# BMS_Adapter_Segment.net
KiCad netlist of a schematic drawn in EAGLE
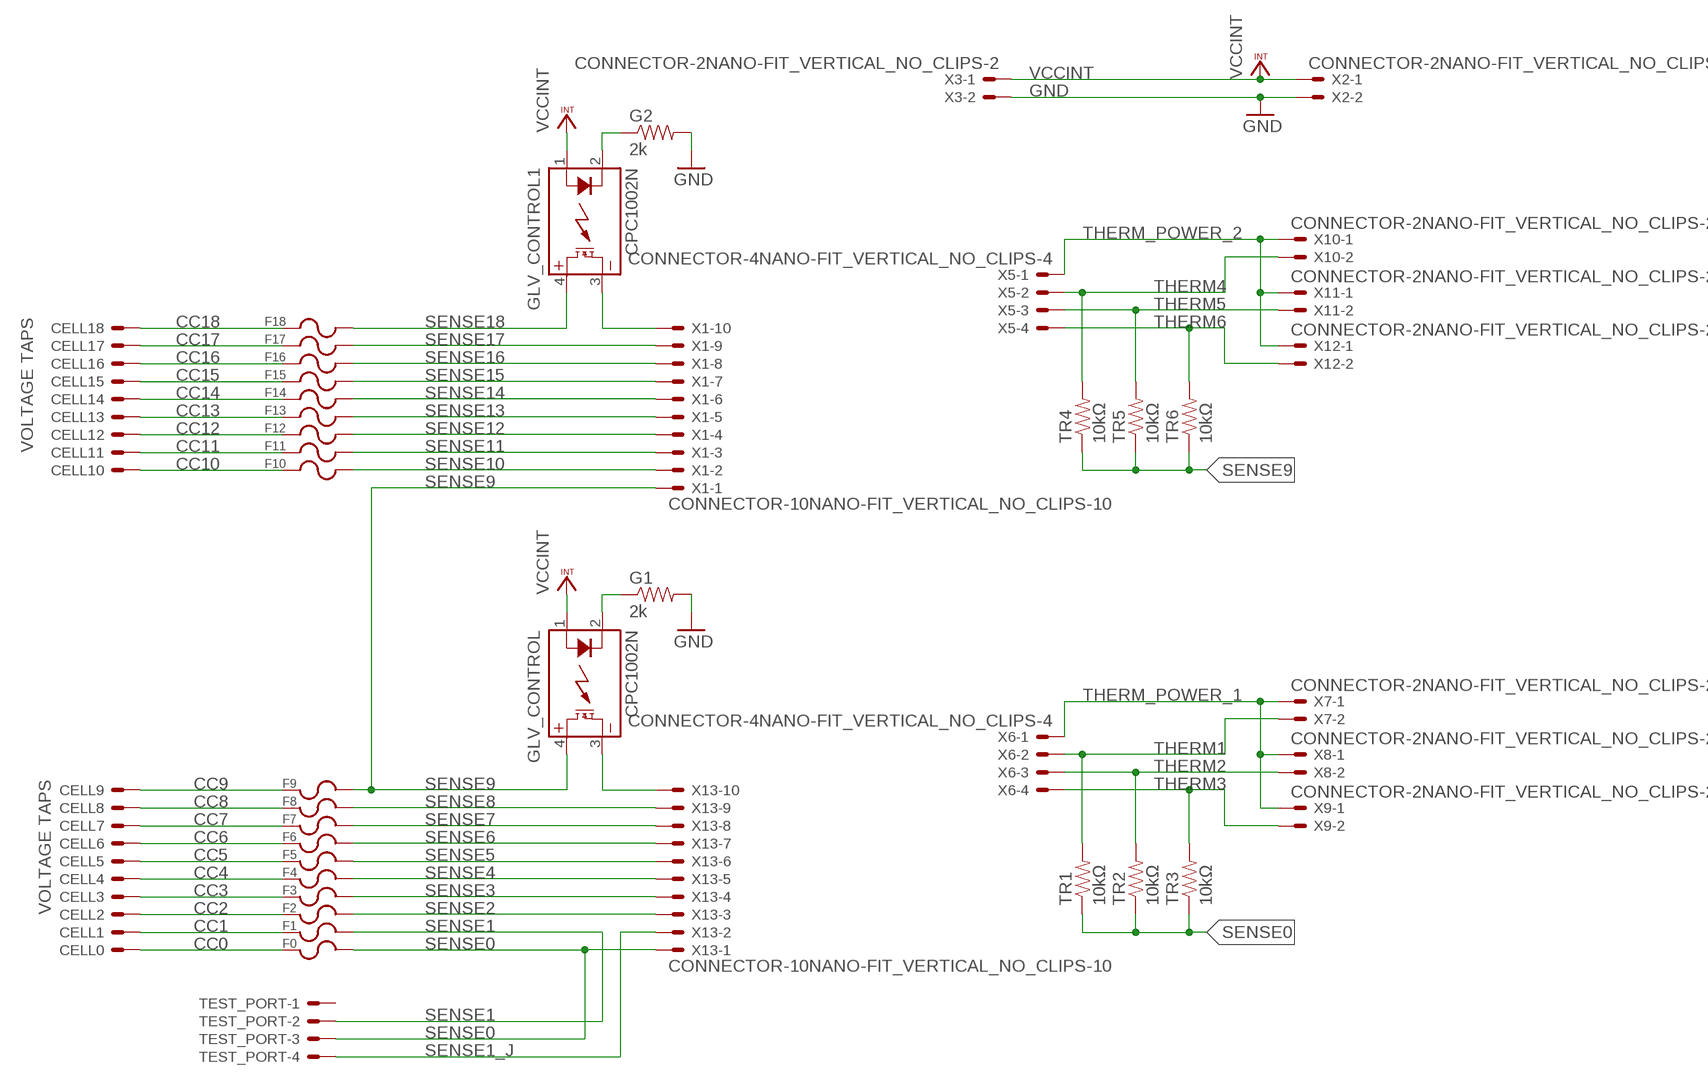
[diagram p0: schematic, sheet 1]

(export (version "E")
  (design (tool "Eeschema 10.0.6"))
  (components
    (comp (ref "CELL0")
      (value "BATTERY_SPRING_KEYSTONE5222")
      (footprint "eagle-import:KEYSTONE5222")
      (libsource (lib "eagle-import") (part "BATTERY_SPRING_KEYSTONE5222"))
    )
    (comp (ref "CELL1")
      (value "BATTERY_SPRING_KEYSTONE5222")
      (footprint "eagle-import:KEYSTONE5222")
      (libsource (lib "eagle-import") (part "BATTERY_SPRING_KEYSTONE5222"))
    )
    (comp (ref "CELL2")
      (value "BATTERY_SPRING_KEYSTONE5222")
      (footprint "eagle-import:KEYSTONE5222")
      (libsource (lib "eagle-import") (part "BATTERY_SPRING_KEYSTONE5222"))
    )
    (comp (ref "CELL3")
      (value "BATTERY_SPRING_KEYSTONE5222")
      (footprint "eagle-import:KEYSTONE5222")
      (libsource (lib "eagle-import") (part "BATTERY_SPRING_KEYSTONE5222"))
    )
    (comp (ref "CELL4")
      (value "BATTERY_SPRING_KEYSTONE5222")
      (footprint "eagle-import:KEYSTONE5222")
      (libsource (lib "eagle-import") (part "BATTERY_SPRING_KEYSTONE5222"))
    )
    (comp (ref "CELL5")
      (value "BATTERY_SPRING_KEYSTONE5222")
      (footprint "eagle-import:KEYSTONE5222")
      (libsource (lib "eagle-import") (part "BATTERY_SPRING_KEYSTONE5222"))
    )
    (comp (ref "CELL6")
      (value "BATTERY_SPRING_KEYSTONE5222")
      (footprint "eagle-import:KEYSTONE5222")
      (libsource (lib "eagle-import") (part "BATTERY_SPRING_KEYSTONE5222"))
    )
    (comp (ref "CELL7")
      (value "BATTERY_SPRING_KEYSTONE5222")
      (footprint "eagle-import:KEYSTONE5222")
      (libsource (lib "eagle-import") (part "BATTERY_SPRING_KEYSTONE5222"))
    )
    (comp (ref "CELL8")
      (value "BATTERY_SPRING_KEYSTONE5222")
      (footprint "eagle-import:KEYSTONE5222")
      (libsource (lib "eagle-import") (part "BATTERY_SPRING_KEYSTONE5222"))
    )
    (comp (ref "CELL9")
      (value "BATTERY_SPRING_KEYSTONE5222")
      (footprint "eagle-import:KEYSTONE5222")
      (libsource (lib "eagle-import") (part "BATTERY_SPRING_KEYSTONE5222"))
    )
    (comp (ref "CELL10")
      (value "BATTERY_SPRING_KEYSTONE5222")
      (footprint "eagle-import:KEYSTONE5222")
      (libsource (lib "eagle-import") (part "BATTERY_SPRING_KEYSTONE5222"))
    )
    (comp (ref "CELL11")
      (value "BATTERY_SPRING_KEYSTONE5222")
      (footprint "eagle-import:KEYSTONE5222")
      (libsource (lib "eagle-import") (part "BATTERY_SPRING_KEYSTONE5222"))
    )
    (comp (ref "CELL12")
      (value "BATTERY_SPRING_KEYSTONE5222")
      (footprint "eagle-import:KEYSTONE5222")
      (libsource (lib "eagle-import") (part "BATTERY_SPRING_KEYSTONE5222"))
    )
    (comp (ref "CELL13")
      (value "BATTERY_SPRING_KEYSTONE5222")
      (footprint "eagle-import:KEYSTONE5222")
      (libsource (lib "eagle-import") (part "BATTERY_SPRING_KEYSTONE5222"))
    )
    (comp (ref "CELL14")
      (value "BATTERY_SPRING_KEYSTONE5222")
      (footprint "eagle-import:KEYSTONE5222")
      (libsource (lib "eagle-import") (part "BATTERY_SPRING_KEYSTONE5222"))
    )
    (comp (ref "CELL15")
      (value "BATTERY_SPRING_KEYSTONE5222")
      (footprint "eagle-import:KEYSTONE5222")
      (libsource (lib "eagle-import") (part "BATTERY_SPRING_KEYSTONE5222"))
    )
    (comp (ref "CELL16")
      (value "BATTERY_SPRING_KEYSTONE5222")
      (footprint "eagle-import:KEYSTONE5222")
      (libsource (lib "eagle-import") (part "BATTERY_SPRING_KEYSTONE5222"))
    )
    (comp (ref "CELL17")
      (value "BATTERY_SPRING_KEYSTONE5222")
      (footprint "eagle-import:KEYSTONE5222")
      (libsource (lib "eagle-import") (part "BATTERY_SPRING_KEYSTONE5222"))
    )
    (comp (ref "CELL18")
      (value "BATTERY_SPRING_KEYSTONE5222")
      (footprint "eagle-import:KEYSTONE5222")
      (libsource (lib "eagle-import") (part "BATTERY_SPRING_KEYSTONE5222"))
    )
    (comp (ref "F0")
      (value "0751.0110_FUSE_CLIP")
      (footprint "eagle-import:0751.0110")
      (libsource (lib "eagle-import") (part "0751.0110_FUSE_CLIP"))
    )
    (comp (ref "F1")
      (value "0751.0110_FUSE_CLIP")
      (footprint "eagle-import:0751.0110")
      (libsource (lib "eagle-import") (part "0751.0110_FUSE_CLIP"))
    )
    (comp (ref "F2")
      (value "0751.0110_FUSE_CLIP")
      (footprint "eagle-import:0751.0110")
      (libsource (lib "eagle-import") (part "0751.0110_FUSE_CLIP"))
    )
    (comp (ref "F3")
      (value "0751.0110_FUSE_CLIP")
      (footprint "eagle-import:0751.0110")
      (libsource (lib "eagle-import") (part "0751.0110_FUSE_CLIP"))
    )
    (comp (ref "F4")
      (value "0751.0110_FUSE_CLIP")
      (footprint "eagle-import:0751.0110")
      (libsource (lib "eagle-import") (part "0751.0110_FUSE_CLIP"))
    )
    (comp (ref "F5")
      (value "0751.0110_FUSE_CLIP")
      (footprint "eagle-import:0751.0110")
      (libsource (lib "eagle-import") (part "0751.0110_FUSE_CLIP"))
    )
    (comp (ref "F6")
      (value "0751.0110_FUSE_CLIP")
      (footprint "eagle-import:0751.0110")
      (libsource (lib "eagle-import") (part "0751.0110_FUSE_CLIP"))
    )
    (comp (ref "F7")
      (value "0751.0110_FUSE_CLIP")
      (footprint "eagle-import:0751.0110")
      (libsource (lib "eagle-import") (part "0751.0110_FUSE_CLIP"))
    )
    (comp (ref "F8")
      (value "0751.0110_FUSE_CLIP")
      (footprint "eagle-import:0751.0110")
      (libsource (lib "eagle-import") (part "0751.0110_FUSE_CLIP"))
    )
    (comp (ref "F9")
      (value "0751.0110_FUSE_CLIP")
      (footprint "eagle-import:0751.0110")
      (libsource (lib "eagle-import") (part "0751.0110_FUSE_CLIP"))
    )
    (comp (ref "F10")
      (value "0751.0110_FUSE_CLIP")
      (footprint "eagle-import:0751.0110")
      (libsource (lib "eagle-import") (part "0751.0110_FUSE_CLIP"))
    )
    (comp (ref "F11")
      (value "0751.0110_FUSE_CLIP")
      (footprint "eagle-import:0751.0110")
      (libsource (lib "eagle-import") (part "0751.0110_FUSE_CLIP"))
    )
    (comp (ref "F12")
      (value "0751.0110_FUSE_CLIP")
      (footprint "eagle-import:0751.0110")
      (libsource (lib "eagle-import") (part "0751.0110_FUSE_CLIP"))
    )
    (comp (ref "F13")
      (value "0751.0110_FUSE_CLIP")
      (footprint "eagle-import:0751.0110")
      (libsource (lib "eagle-import") (part "0751.0110_FUSE_CLIP"))
    )
    (comp (ref "F14")
      (value "0751.0110_FUSE_CLIP")
      (footprint "eagle-import:0751.0110")
      (libsource (lib "eagle-import") (part "0751.0110_FUSE_CLIP"))
    )
    (comp (ref "F15")
      (value "0751.0110_FUSE_CLIP")
      (footprint "eagle-import:0751.0110")
      (libsource (lib "eagle-import") (part "0751.0110_FUSE_CLIP"))
    )
    (comp (ref "F16")
      (value "0751.0110_FUSE_CLIP")
      (footprint "eagle-import:0751.0110")
      (libsource (lib "eagle-import") (part "0751.0110_FUSE_CLIP"))
    )
    (comp (ref "F17")
      (value "0751.0110_FUSE_CLIP")
      (footprint "eagle-import:0751.0110")
      (libsource (lib "eagle-import") (part "0751.0110_FUSE_CLIP"))
    )
    (comp (ref "F18")
      (value "0751.0110_FUSE_CLIP")
      (footprint "eagle-import:0751.0110")
      (libsource (lib "eagle-import") (part "0751.0110_FUSE_CLIP"))
    )
    (comp (ref "G1")
      (value "2k")
      (footprint "eagle-import:0805")
      (libsource (lib "eagle-import") (part "RESISTOR0805-RES"))
    )
    (comp (ref "G2")
      (value "2k")
      (footprint "eagle-import:0805")
      (libsource (lib "eagle-import") (part "RESISTOR0805-RES"))
    )
    (comp (ref "GLV_CONTROL")
      (value "CPC1002N")
      (footprint "eagle-import:SOP04")
      (libsource (lib "eagle-import") (part "CPC1002N"))
    )
    (comp (ref "GLV_CONTROL1")
      (value "CPC1002N")
      (footprint "eagle-import:SOP04")
      (libsource (lib "eagle-import") (part "CPC1002N"))
    )
    (comp (ref "TEST_PORT")
      (value "MINIFIT_5566-4")
      (footprint "eagle-import:MINIFIT_5566-4")
      (libsource (lib "eagle-import") (part "MINIFIT_5566-4"))
    )
    (comp (ref "TR1")
      (value "10kΩ")
      (footprint "eagle-import:0805")
      (libsource (lib "eagle-import") (part "RESISTOR0805-RES"))
    )
    (comp (ref "TR2")
      (value "10kΩ")
      (footprint "eagle-import:0805")
      (libsource (lib "eagle-import") (part "RESISTOR0805-RES"))
    )
    (comp (ref "TR3")
      (value "10kΩ")
      (footprint "eagle-import:0805")
      (libsource (lib "eagle-import") (part "RESISTOR0805-RES"))
    )
    (comp (ref "TR4")
      (value "10kΩ")
      (footprint "eagle-import:0805")
      (libsource (lib "eagle-import") (part "RESISTOR0805-RES"))
    )
    (comp (ref "TR5")
      (value "10kΩ")
      (footprint "eagle-import:0805")
      (libsource (lib "eagle-import") (part "RESISTOR0805-RES"))
    )
    (comp (ref "TR6")
      (value "10kΩ")
      (footprint "eagle-import:0805")
      (libsource (lib "eagle-import") (part "RESISTOR0805-RES"))
    )
    (comp (ref "X1")
      (value "CONNECTOR-10NANO-FIT_VERTICAL_NO_CLIPS-10")
      (footprint "eagle-import:NANO-FIT_VERTICAL_NO_CLIPS-10")
      (libsource (lib "eagle-import") (part "CONNECTOR-10NANO-FIT_VERTICAL_NO_CLIPS-10"))
    )
    (comp (ref "X2")
      (value "CONNECTOR-2NANO-FIT_VERTICAL_NO_CLIPS-2")
      (footprint "eagle-import:NANO-FIT_VERTICAL_NO_CLIPS-2")
      (libsource (lib "eagle-import") (part "CONNECTOR-2NANO-FIT_VERTICAL_NO_CLIPS-2"))
    )
    (comp (ref "X3")
      (value "CONNECTOR-2NANO-FIT_VERTICAL_NO_CLIPS-2")
      (footprint "eagle-import:NANO-FIT_VERTICAL_NO_CLIPS-2")
      (libsource (lib "eagle-import") (part "CONNECTOR-2NANO-FIT_VERTICAL_NO_CLIPS-2"))
    )
    (comp (ref "X5")
      (value "CONNECTOR-4NANO-FIT_VERTICAL_NO_CLIPS-4")
      (footprint "eagle-import:NANO-FIT_VERTICAL_NO_CLIPS-4")
      (libsource (lib "eagle-import") (part "CONNECTOR-4NANO-FIT_VERTICAL_NO_CLIPS-4"))
    )
    (comp (ref "X6")
      (value "CONNECTOR-4NANO-FIT_VERTICAL_NO_CLIPS-4")
      (footprint "eagle-import:NANO-FIT_VERTICAL_NO_CLIPS-4")
      (libsource (lib "eagle-import") (part "CONNECTOR-4NANO-FIT_VERTICAL_NO_CLIPS-4"))
    )
    (comp (ref "X7")
      (value "CONNECTOR-2NANO-FIT_VERTICAL_NO_CLIPS-2")
      (footprint "eagle-import:NANO-FIT_VERTICAL_NO_CLIPS-2")
      (libsource (lib "eagle-import") (part "CONNECTOR-2NANO-FIT_VERTICAL_NO_CLIPS-2"))
    )
    (comp (ref "X8")
      (value "CONNECTOR-2NANO-FIT_VERTICAL_NO_CLIPS-2")
      (footprint "eagle-import:NANO-FIT_VERTICAL_NO_CLIPS-2")
      (libsource (lib "eagle-import") (part "CONNECTOR-2NANO-FIT_VERTICAL_NO_CLIPS-2"))
    )
    (comp (ref "X9")
      (value "CONNECTOR-2NANO-FIT_VERTICAL_NO_CLIPS-2")
      (footprint "eagle-import:NANO-FIT_VERTICAL_NO_CLIPS-2")
      (libsource (lib "eagle-import") (part "CONNECTOR-2NANO-FIT_VERTICAL_NO_CLIPS-2"))
    )
    (comp (ref "X10")
      (value "CONNECTOR-2NANO-FIT_VERTICAL_NO_CLIPS-2")
      (footprint "eagle-import:NANO-FIT_VERTICAL_NO_CLIPS-2")
      (libsource (lib "eagle-import") (part "CONNECTOR-2NANO-FIT_VERTICAL_NO_CLIPS-2"))
    )
    (comp (ref "X11")
      (value "CONNECTOR-2NANO-FIT_VERTICAL_NO_CLIPS-2")
      (footprint "eagle-import:NANO-FIT_VERTICAL_NO_CLIPS-2")
      (libsource (lib "eagle-import") (part "CONNECTOR-2NANO-FIT_VERTICAL_NO_CLIPS-2"))
    )
    (comp (ref "X12")
      (value "CONNECTOR-2NANO-FIT_VERTICAL_NO_CLIPS-2")
      (footprint "eagle-import:NANO-FIT_VERTICAL_NO_CLIPS-2")
      (libsource (lib "eagle-import") (part "CONNECTOR-2NANO-FIT_VERTICAL_NO_CLIPS-2"))
    )
    (comp (ref "X13")
      (value "CONNECTOR-10NANO-FIT_VERTICAL_NO_CLIPS-10")
      (footprint "eagle-import:NANO-FIT_VERTICAL_NO_CLIPS-10")
      (libsource (lib "eagle-import") (part "CONNECTOR-10NANO-FIT_VERTICAL_NO_CLIPS-10"))
    )
  )
  (nets
    (net (code "1") (name "/CC0") (class "Default")
      (node (ref "CELL0") (pin "P$1") (pinfunction "S_P$1") (pintype "passive"))
      (node (ref "F0") (pin "L1") (pinfunction "1_L1") (pintype "bidirectional"))
      (node (ref "F0") (pin "L2") (pinfunction "1_L2") (pintype "bidirectional"))
    )
    (net (code "2") (name "/CC1") (class "Default")
      (node (ref "CELL1") (pin "P$1") (pinfunction "S_P$1") (pintype "passive"))
      (node (ref "F1") (pin "L1") (pinfunction "1_L1") (pintype "bidirectional"))
      (node (ref "F1") (pin "L2") (pinfunction "1_L2") (pintype "bidirectional"))
    )
    (net (code "3") (name "/CC2") (class "Default")
      (node (ref "CELL2") (pin "P$1") (pinfunction "S_P$1") (pintype "passive"))
      (node (ref "F2") (pin "L1") (pinfunction "1_L1") (pintype "bidirectional"))
      (node (ref "F2") (pin "L2") (pinfunction "1_L2") (pintype "bidirectional"))
    )
    (net (code "4") (name "/CC3") (class "Default")
      (node (ref "CELL3") (pin "P$1") (pinfunction "S_P$1") (pintype "passive"))
      (node (ref "F3") (pin "L1") (pinfunction "1_L1") (pintype "bidirectional"))
      (node (ref "F3") (pin "L2") (pinfunction "1_L2") (pintype "bidirectional"))
    )
    (net (code "5") (name "/CC4") (class "Default")
      (node (ref "CELL4") (pin "P$1") (pinfunction "S_P$1") (pintype "passive"))
      (node (ref "F4") (pin "L1") (pinfunction "1_L1") (pintype "bidirectional"))
      (node (ref "F4") (pin "L2") (pinfunction "1_L2") (pintype "bidirectional"))
    )
    (net (code "6") (name "/CC5") (class "Default")
      (node (ref "CELL5") (pin "P$1") (pinfunction "S_P$1") (pintype "passive"))
      (node (ref "F5") (pin "L1") (pinfunction "1_L1") (pintype "bidirectional"))
      (node (ref "F5") (pin "L2") (pinfunction "1_L2") (pintype "bidirectional"))
    )
    (net (code "7") (name "/CC6") (class "Default")
      (node (ref "CELL6") (pin "P$1") (pinfunction "S_P$1") (pintype "passive"))
      (node (ref "F6") (pin "L1") (pinfunction "1_L1") (pintype "bidirectional"))
      (node (ref "F6") (pin "L2") (pinfunction "1_L2") (pintype "bidirectional"))
    )
    (net (code "8") (name "/CC7") (class "Default")
      (node (ref "CELL7") (pin "P$1") (pinfunction "S_P$1") (pintype "passive"))
      (node (ref "F7") (pin "L1") (pinfunction "1_L1") (pintype "bidirectional"))
      (node (ref "F7") (pin "L2") (pinfunction "1_L2") (pintype "bidirectional"))
    )
    (net (code "9") (name "/CC8") (class "Default")
      (node (ref "CELL8") (pin "P$1") (pinfunction "S_P$1") (pintype "passive"))
      (node (ref "F8") (pin "L1") (pinfunction "1_L1") (pintype "bidirectional"))
      (node (ref "F8") (pin "L2") (pinfunction "1_L2") (pintype "bidirectional"))
    )
    (net (code "10") (name "/CC9") (class "Default")
      (node (ref "CELL9") (pin "P$1") (pinfunction "S_P$1") (pintype "passive"))
      (node (ref "F9") (pin "L1") (pinfunction "1_L1") (pintype "bidirectional"))
      (node (ref "F9") (pin "L2") (pinfunction "1_L2") (pintype "bidirectional"))
    )
    (net (code "11") (name "/CC10") (class "Default")
      (node (ref "CELL10") (pin "P$1") (pinfunction "S_P$1") (pintype "passive"))
      (node (ref "F10") (pin "L1") (pinfunction "1_L1") (pintype "bidirectional"))
      (node (ref "F10") (pin "L2") (pinfunction "1_L2") (pintype "bidirectional"))
    )
    (net (code "12") (name "/CC11") (class "Default")
      (node (ref "CELL11") (pin "P$1") (pinfunction "S_P$1") (pintype "passive"))
      (node (ref "F11") (pin "L1") (pinfunction "1_L1") (pintype "bidirectional"))
      (node (ref "F11") (pin "L2") (pinfunction "1_L2") (pintype "bidirectional"))
    )
    (net (code "13") (name "/CC12") (class "Default")
      (node (ref "CELL12") (pin "P$1") (pinfunction "S_P$1") (pintype "passive"))
      (node (ref "F12") (pin "L1") (pinfunction "1_L1") (pintype "bidirectional"))
      (node (ref "F12") (pin "L2") (pinfunction "1_L2") (pintype "bidirectional"))
    )
    (net (code "14") (name "/CC13") (class "Default")
      (node (ref "CELL13") (pin "P$1") (pinfunction "S_P$1") (pintype "passive"))
      (node (ref "F13") (pin "L1") (pinfunction "1_L1") (pintype "bidirectional"))
      (node (ref "F13") (pin "L2") (pinfunction "1_L2") (pintype "bidirectional"))
    )
    (net (code "15") (name "/CC14") (class "Default")
      (node (ref "CELL14") (pin "P$1") (pinfunction "S_P$1") (pintype "passive"))
      (node (ref "F14") (pin "L1") (pinfunction "1_L1") (pintype "bidirectional"))
      (node (ref "F14") (pin "L2") (pinfunction "1_L2") (pintype "bidirectional"))
    )
    (net (code "16") (name "/CC15") (class "Default")
      (node (ref "CELL15") (pin "P$1") (pinfunction "S_P$1") (pintype "passive"))
      (node (ref "F15") (pin "L1") (pinfunction "1_L1") (pintype "bidirectional"))
      (node (ref "F15") (pin "L2") (pinfunction "1_L2") (pintype "bidirectional"))
    )
    (net (code "17") (name "/CC16") (class "Default")
      (node (ref "CELL16") (pin "P$1") (pinfunction "S_P$1") (pintype "passive"))
      (node (ref "F16") (pin "L1") (pinfunction "1_L1") (pintype "bidirectional"))
      (node (ref "F16") (pin "L2") (pinfunction "1_L2") (pintype "bidirectional"))
    )
    (net (code "18") (name "/CC17") (class "Default")
      (node (ref "CELL17") (pin "P$1") (pinfunction "S_P$1") (pintype "passive"))
      (node (ref "F17") (pin "L1") (pinfunction "1_L1") (pintype "bidirectional"))
      (node (ref "F17") (pin "L2") (pinfunction "1_L2") (pintype "bidirectional"))
    )
    (net (code "19") (name "/CC18") (class "Default")
      (node (ref "CELL18") (pin "P$1") (pinfunction "S_P$1") (pintype "passive"))
      (node (ref "F18") (pin "L1") (pinfunction "1_L1") (pintype "bidirectional"))
      (node (ref "F18") (pin "L2") (pinfunction "1_L2") (pintype "bidirectional"))
    )
    (net (code "20") (name "/SENSE1") (class "Default")
      (node (ref "F1") (pin "R1") (pinfunction "2_R1") (pintype "bidirectional"))
      (node (ref "F1") (pin "R2") (pinfunction "2_R2") (pintype "bidirectional"))
      (node (ref "TEST_PORT") (pin "2") (pinfunction "S_2") (pintype "passive"))
    )
    (net (code "21") (name "/SENSE1_J") (class "Default")
      (node (ref "TEST_PORT") (pin "4") (pinfunction "S_4") (pintype "passive"))
      (node (ref "X13") (pin "P$2") (pinfunction "S_P$2") (pintype "passive"))
    )
    (net (code "22") (name "/SENSE2") (class "Default")
      (node (ref "F2") (pin "R1") (pinfunction "2_R1") (pintype "bidirectional"))
      (node (ref "F2") (pin "R2") (pinfunction "2_R2") (pintype "bidirectional"))
      (node (ref "X13") (pin "P$3") (pinfunction "S_P$3") (pintype "passive"))
    )
    (net (code "23") (name "/SENSE3") (class "Default")
      (node (ref "F3") (pin "R1") (pinfunction "2_R1") (pintype "bidirectional"))
      (node (ref "F3") (pin "R2") (pinfunction "2_R2") (pintype "bidirectional"))
      (node (ref "X13") (pin "P$4") (pinfunction "S_P$4") (pintype "passive"))
    )
    (net (code "24") (name "/SENSE4") (class "Default")
      (node (ref "F4") (pin "R1") (pinfunction "2_R1") (pintype "bidirectional"))
      (node (ref "F4") (pin "R2") (pinfunction "2_R2") (pintype "bidirectional"))
      (node (ref "X13") (pin "P$5") (pinfunction "S_P$5") (pintype "passive"))
    )
    (net (code "25") (name "/SENSE5") (class "Default")
      (node (ref "F5") (pin "R1") (pinfunction "2_R1") (pintype "bidirectional"))
      (node (ref "F5") (pin "R2") (pinfunction "2_R2") (pintype "bidirectional"))
      (node (ref "X13") (pin "P$6") (pinfunction "S_P$6") (pintype "passive"))
    )
    (net (code "26") (name "/SENSE6") (class "Default")
      (node (ref "F6") (pin "R1") (pinfunction "2_R1") (pintype "bidirectional"))
      (node (ref "F6") (pin "R2") (pinfunction "2_R2") (pintype "bidirectional"))
      (node (ref "X13") (pin "P$7") (pinfunction "S_P$7") (pintype "passive"))
    )
    (net (code "27") (name "/SENSE7") (class "Default")
      (node (ref "F7") (pin "R1") (pinfunction "2_R1") (pintype "bidirectional"))
      (node (ref "F7") (pin "R2") (pinfunction "2_R2") (pintype "bidirectional"))
      (node (ref "X13") (pin "P$8") (pinfunction "S_P$8") (pintype "passive"))
    )
    (net (code "28") (name "/SENSE8") (class "Default")
      (node (ref "F8") (pin "R1") (pinfunction "2_R1") (pintype "bidirectional"))
      (node (ref "F8") (pin "R2") (pinfunction "2_R2") (pintype "bidirectional"))
      (node (ref "X13") (pin "P$9") (pinfunction "S_P$9") (pintype "passive"))
    )
    (net (code "29") (name "/SENSE10") (class "Default")
      (node (ref "F10") (pin "R1") (pinfunction "2_R1") (pintype "bidirectional"))
      (node (ref "F10") (pin "R2") (pinfunction "2_R2") (pintype "bidirectional"))
      (node (ref "X1") (pin "P$2") (pinfunction "S_P$2") (pintype "passive"))
    )
    (net (code "30") (name "/SENSE11") (class "Default")
      (node (ref "F11") (pin "R1") (pinfunction "2_R1") (pintype "bidirectional"))
      (node (ref "F11") (pin "R2") (pinfunction "2_R2") (pintype "bidirectional"))
      (node (ref "X1") (pin "P$3") (pinfunction "S_P$3") (pintype "passive"))
    )
    (net (code "31") (name "/SENSE12") (class "Default")
      (node (ref "F12") (pin "R1") (pinfunction "2_R1") (pintype "bidirectional"))
      (node (ref "F12") (pin "R2") (pinfunction "2_R2") (pintype "bidirectional"))
      (node (ref "X1") (pin "P$4") (pinfunction "S_P$4") (pintype "passive"))
    )
    (net (code "32") (name "/SENSE13") (class "Default")
      (node (ref "F13") (pin "R1") (pinfunction "2_R1") (pintype "bidirectional"))
      (node (ref "F13") (pin "R2") (pinfunction "2_R2") (pintype "bidirectional"))
      (node (ref "X1") (pin "P$5") (pinfunction "S_P$5") (pintype "passive"))
    )
    (net (code "33") (name "/SENSE14") (class "Default")
      (node (ref "F14") (pin "R1") (pinfunction "2_R1") (pintype "bidirectional"))
      (node (ref "F14") (pin "R2") (pinfunction "2_R2") (pintype "bidirectional"))
      (node (ref "X1") (pin "P$6") (pinfunction "S_P$6") (pintype "passive"))
    )
    (net (code "34") (name "/SENSE15") (class "Default")
      (node (ref "F15") (pin "R1") (pinfunction "2_R1") (pintype "bidirectional"))
      (node (ref "F15") (pin "R2") (pinfunction "2_R2") (pintype "bidirectional"))
      (node (ref "X1") (pin "P$7") (pinfunction "S_P$7") (pintype "passive"))
    )
    (net (code "35") (name "/SENSE16") (class "Default")
      (node (ref "F16") (pin "R1") (pinfunction "2_R1") (pintype "bidirectional"))
      (node (ref "F16") (pin "R2") (pinfunction "2_R2") (pintype "bidirectional"))
      (node (ref "X1") (pin "P$8") (pinfunction "S_P$8") (pintype "passive"))
    )
    (net (code "36") (name "/SENSE17") (class "Default")
      (node (ref "F17") (pin "R1") (pinfunction "2_R1") (pintype "bidirectional"))
      (node (ref "F17") (pin "R2") (pinfunction "2_R2") (pintype "bidirectional"))
      (node (ref "X1") (pin "P$9") (pinfunction "S_P$9") (pintype "passive"))
    )
    (net (code "37") (name "/SENSE18") (class "Default")
      (node (ref "F18") (pin "R1") (pinfunction "2_R1") (pintype "bidirectional"))
      (node (ref "F18") (pin "R2") (pinfunction "2_R2") (pintype "bidirectional"))
      (node (ref "GLV_CONTROL1") (pin "4") (pinfunction "DC+_4") (pintype "passive"))
    )
    (net (code "38") (name "/THERM1") (class "Default")
      (node (ref "TR1") (pin "2") (pinfunction "2_2") (pintype "passive"))
      (node (ref "X6") (pin "P$2") (pinfunction "S_P$2") (pintype "passive"))
      (node (ref "X7") (pin "P$2") (pinfunction "S_P$2") (pintype "passive"))
    )
    (net (code "39") (name "/THERM2") (class "Default")
      (node (ref "TR2") (pin "2") (pinfunction "2_2") (pintype "passive"))
      (node (ref "X6") (pin "P$3") (pinfunction "S_P$3") (pintype "passive"))
      (node (ref "X8") (pin "P$2") (pinfunction "S_P$2") (pintype "passive"))
    )
    (net (code "40") (name "/THERM3") (class "Default")
      (node (ref "TR3") (pin "2") (pinfunction "2_2") (pintype "passive"))
      (node (ref "X6") (pin "P$4") (pinfunction "S_P$4") (pintype "passive"))
      (node (ref "X9") (pin "P$2") (pinfunction "S_P$2") (pintype "passive"))
    )
    (net (code "41") (name "/THERM4") (class "Default")
      (node (ref "TR4") (pin "2") (pinfunction "2_2") (pintype "passive"))
      (node (ref "X10") (pin "P$2") (pinfunction "S_P$2") (pintype "passive"))
      (node (ref "X5") (pin "P$2") (pinfunction "S_P$2") (pintype "passive"))
    )
    (net (code "42") (name "/THERM5") (class "Default")
      (node (ref "TR5") (pin "2") (pinfunction "2_2") (pintype "passive"))
      (node (ref "X11") (pin "P$2") (pinfunction "S_P$2") (pintype "passive"))
      (node (ref "X5") (pin "P$3") (pinfunction "S_P$3") (pintype "passive"))
    )
    (net (code "43") (name "/THERM6") (class "Default")
      (node (ref "TR6") (pin "2") (pinfunction "2_2") (pintype "passive"))
      (node (ref "X12") (pin "P$2") (pinfunction "S_P$2") (pintype "passive"))
      (node (ref "X5") (pin "P$4") (pinfunction "S_P$4") (pintype "passive"))
    )
    (net (code "44") (name "/THERM_POWER_1") (class "Default")
      (node (ref "X6") (pin "P$1") (pinfunction "S_P$1") (pintype "passive"))
      (node (ref "X7") (pin "P$1") (pinfunction "S_P$1") (pintype "passive"))
      (node (ref "X8") (pin "P$1") (pinfunction "S_P$1") (pintype "passive"))
      (node (ref "X9") (pin "P$1") (pinfunction "S_P$1") (pintype "passive"))
    )
    (net (code "45") (name "/THERM_POWER_2") (class "Default")
      (node (ref "X10") (pin "P$1") (pinfunction "S_P$1") (pintype "passive"))
      (node (ref "X11") (pin "P$1") (pinfunction "S_P$1") (pintype "passive"))
      (node (ref "X12") (pin "P$1") (pinfunction "S_P$1") (pintype "passive"))
      (node (ref "X5") (pin "P$1") (pinfunction "S_P$1") (pintype "passive"))
    )
    (net (code "46") (name "GND") (class "Default")
      (node (ref "G1") (pin "2") (pinfunction "2_2") (pintype "passive"))
      (node (ref "G2") (pin "2") (pinfunction "2_2") (pintype "passive"))
      (node (ref "X2") (pin "P$2") (pinfunction "S_P$2") (pintype "passive"))
      (node (ref "X3") (pin "P$2") (pinfunction "S_P$2") (pintype "passive"))
    )
    (net (code "47") (name "Net-(GLV_CONTROL-CONTROL-)") (class "Default")
      (node (ref "G1") (pin "1") (pinfunction "1_1") (pintype "passive"))
      (node (ref "GLV_CONTROL") (pin "2") (pinfunction "CONTROL-_2") (pintype "passive"))
    )
    (net (code "48") (name "Net-(GLV_CONTROL-DC-)") (class "Default")
      (node (ref "GLV_CONTROL") (pin "3") (pinfunction "DC-_3") (pintype "passive"))
      (node (ref "X13") (pin "P$10") (pinfunction "S_P$10") (pintype "passive"))
    )
    (net (code "49") (name "Net-(GLV_CONTROL1-CONTROL-)") (class "Default")
      (node (ref "G2") (pin "1") (pinfunction "1_1") (pintype "passive"))
      (node (ref "GLV_CONTROL1") (pin "2") (pinfunction "CONTROL-_2") (pintype "passive"))
    )
    (net (code "50") (name "Net-(GLV_CONTROL1-DC-)") (class "Default")
      (node (ref "GLV_CONTROL1") (pin "3") (pinfunction "DC-_3") (pintype "passive"))
      (node (ref "X1") (pin "P$10") (pinfunction "S_P$10") (pintype "passive"))
    )
    (net (code "51") (name "SENSE0") (class "Default")
      (node (ref "F0") (pin "R1") (pinfunction "2_R1") (pintype "bidirectional"))
      (node (ref "F0") (pin "R2") (pinfunction "2_R2") (pintype "bidirectional"))
      (node (ref "TEST_PORT") (pin "3") (pinfunction "S_3") (pintype "passive"))
      (node (ref "TR1") (pin "1") (pinfunction "1_1") (pintype "passive"))
      (node (ref "TR2") (pin "1") (pinfunction "1_1") (pintype "passive"))
      (node (ref "TR3") (pin "1") (pinfunction "1_1") (pintype "passive"))
      (node (ref "X13") (pin "P$1") (pinfunction "S_P$1") (pintype "passive"))
    )
    (net (code "52") (name "SENSE9") (class "Default")
      (node (ref "F9") (pin "R1") (pinfunction "2_R1") (pintype "bidirectional"))
      (node (ref "F9") (pin "R2") (pinfunction "2_R2") (pintype "bidirectional"))
      (node (ref "GLV_CONTROL") (pin "4") (pinfunction "DC+_4") (pintype "passive"))
      (node (ref "TR4") (pin "1") (pinfunction "1_1") (pintype "passive"))
      (node (ref "TR5") (pin "1") (pinfunction "1_1") (pintype "passive"))
      (node (ref "TR6") (pin "1") (pinfunction "1_1") (pintype "passive"))
      (node (ref "X1") (pin "P$1") (pinfunction "S_P$1") (pintype "passive"))
    )
    (net (code "53") (name "VCCINT") (class "Default")
      (node (ref "GLV_CONTROL") (pin "1") (pinfunction "CONTROL+_1") (pintype "passive"))
      (node (ref "GLV_CONTROL1") (pin "1") (pinfunction "CONTROL+_1") (pintype "passive"))
      (node (ref "X2") (pin "P$1") (pinfunction "S_P$1") (pintype "passive"))
      (node (ref "X3") (pin "P$1") (pinfunction "S_P$1") (pintype "passive"))
    )
    (net (code "54") (name "unconnected-(TEST_PORTA-S-Pad1)") (class "Default")
      (node (ref "TEST_PORT") (pin "1") (pinfunction "S_1") (pintype "passive"))
    )
  )
)
